# Keyboard.net
KiCad netlist of a schematic drawn in Altium Designer
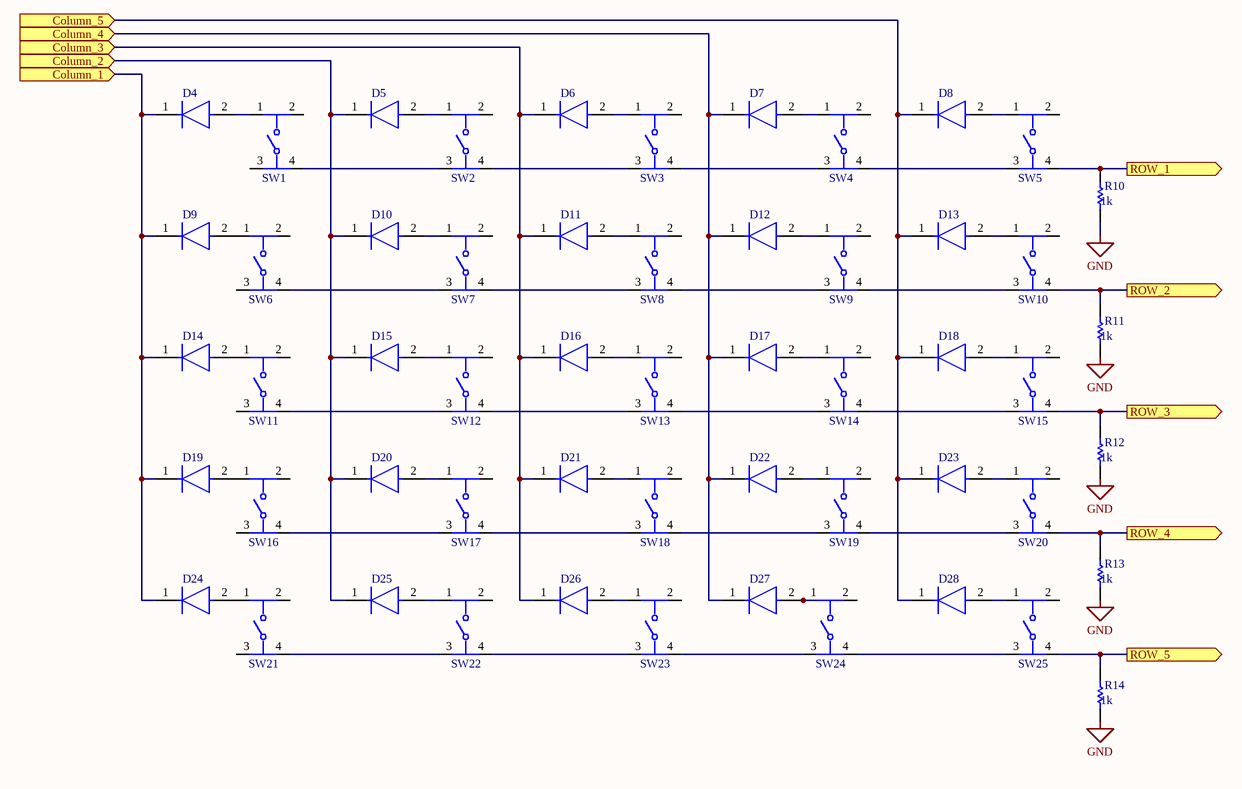
[diagram p0: Keyboard.SchDoc]

(export (version "E")
  (design (tool "Eeschema 10.0.6"))
  (components
    (comp (ref "D4")
      (value "TS4148 RYG")
      (footprint "FP-TS4148_RYG-MFG")
      (description "Rectifier Diode Switching 75V 0.15A 4ns 2-Pin Case 0805(2012Metric) T/R")
      (libsource (lib "Altium Content Vault") (part "d7152d700b627762746794eb795d46e"))
    )
    (comp (ref "D5")
      (value "TS4148 RYG")
      (footprint "FP-TS4148_RYG-MFG")
      (description "Rectifier Diode Switching 75V 0.15A 4ns 2-Pin Case 0805(2012Metric) T/R")
      (libsource (lib "Altium Content Vault") (part "d7152d700b627762746794eb795d46e"))
    )
    (comp (ref "D6")
      (value "TS4148 RYG")
      (footprint "FP-TS4148_RYG-MFG")
      (description "Rectifier Diode Switching 75V 0.15A 4ns 2-Pin Case 0805(2012Metric) T/R")
      (libsource (lib "Altium Content Vault") (part "d7152d700b627762746794eb795d46e"))
    )
    (comp (ref "D7")
      (value "TS4148 RYG")
      (footprint "FP-TS4148_RYG-MFG")
      (description "Rectifier Diode Switching 75V 0.15A 4ns 2-Pin Case 0805(2012Metric) T/R")
      (libsource (lib "Altium Content Vault") (part "d7152d700b627762746794eb795d46e"))
    )
    (comp (ref "D8")
      (value "TS4148 RYG")
      (footprint "FP-TS4148_RYG-MFG")
      (description "Rectifier Diode Switching 75V 0.15A 4ns 2-Pin Case 0805(2012Metric) T/R")
      (libsource (lib "Altium Content Vault") (part "d7152d700b627762746794eb795d46e"))
    )
    (comp (ref "D9")
      (value "TS4148 RYG")
      (footprint "FP-TS4148_RYG-MFG")
      (description "Rectifier Diode Switching 75V 0.15A 4ns 2-Pin Case 0805(2012Metric) T/R")
      (libsource (lib "Altium Content Vault") (part "d7152d700b627762746794eb795d46e"))
    )
    (comp (ref "D10")
      (value "TS4148 RYG")
      (footprint "FP-TS4148_RYG-MFG")
      (description "Rectifier Diode Switching 75V 0.15A 4ns 2-Pin Case 0805(2012Metric) T/R")
      (libsource (lib "Altium Content Vault") (part "d7152d700b627762746794eb795d46e"))
    )
    (comp (ref "D11")
      (value "TS4148 RYG")
      (footprint "FP-TS4148_RYG-MFG")
      (description "Rectifier Diode Switching 75V 0.15A 4ns 2-Pin Case 0805(2012Metric) T/R")
      (libsource (lib "Altium Content Vault") (part "d7152d700b627762746794eb795d46e"))
    )
    (comp (ref "D12")
      (value "TS4148 RYG")
      (footprint "FP-TS4148_RYG-MFG")
      (description "Rectifier Diode Switching 75V 0.15A 4ns 2-Pin Case 0805(2012Metric) T/R")
      (libsource (lib "Altium Content Vault") (part "d7152d700b627762746794eb795d46e"))
    )
    (comp (ref "D13")
      (value "TS4148 RYG")
      (footprint "FP-TS4148_RYG-MFG")
      (description "Rectifier Diode Switching 75V 0.15A 4ns 2-Pin Case 0805(2012Metric) T/R")
      (libsource (lib "Altium Content Vault") (part "d7152d700b627762746794eb795d46e"))
    )
    (comp (ref "D14")
      (value "TS4148 RYG")
      (footprint "FP-TS4148_RYG-MFG")
      (description "Rectifier Diode Switching 75V 0.15A 4ns 2-Pin Case 0805(2012Metric) T/R")
      (libsource (lib "Altium Content Vault") (part "d7152d700b627762746794eb795d46e"))
    )
    (comp (ref "D15")
      (value "TS4148 RYG")
      (footprint "FP-TS4148_RYG-MFG")
      (description "Rectifier Diode Switching 75V 0.15A 4ns 2-Pin Case 0805(2012Metric) T/R")
      (libsource (lib "Altium Content Vault") (part "d7152d700b627762746794eb795d46e"))
    )
    (comp (ref "D16")
      (value "TS4148 RYG")
      (footprint "FP-TS4148_RYG-MFG")
      (description "Rectifier Diode Switching 75V 0.15A 4ns 2-Pin Case 0805(2012Metric) T/R")
      (libsource (lib "Altium Content Vault") (part "d7152d700b627762746794eb795d46e"))
    )
    (comp (ref "D17")
      (value "TS4148 RYG")
      (footprint "FP-TS4148_RYG-MFG")
      (description "Rectifier Diode Switching 75V 0.15A 4ns 2-Pin Case 0805(2012Metric) T/R")
      (libsource (lib "Altium Content Vault") (part "d7152d700b627762746794eb795d46e"))
    )
    (comp (ref "D18")
      (value "TS4148 RYG")
      (footprint "FP-TS4148_RYG-MFG")
      (description "Rectifier Diode Switching 75V 0.15A 4ns 2-Pin Case 0805(2012Metric) T/R")
      (libsource (lib "Altium Content Vault") (part "d7152d700b627762746794eb795d46e"))
    )
    (comp (ref "D19")
      (value "TS4148 RYG")
      (footprint "FP-TS4148_RYG-MFG")
      (description "Rectifier Diode Switching 75V 0.15A 4ns 2-Pin Case 0805(2012Metric) T/R")
      (libsource (lib "Altium Content Vault") (part "d7152d700b627762746794eb795d46e"))
    )
    (comp (ref "D20")
      (value "TS4148 RYG")
      (footprint "FP-TS4148_RYG-MFG")
      (description "Rectifier Diode Switching 75V 0.15A 4ns 2-Pin Case 0805(2012Metric) T/R")
      (libsource (lib "Altium Content Vault") (part "d7152d700b627762746794eb795d46e"))
    )
    (comp (ref "D21")
      (value "TS4148 RYG")
      (footprint "FP-TS4148_RYG-MFG")
      (description "Rectifier Diode Switching 75V 0.15A 4ns 2-Pin Case 0805(2012Metric) T/R")
      (libsource (lib "Altium Content Vault") (part "d7152d700b627762746794eb795d46e"))
    )
    (comp (ref "D22")
      (value "TS4148 RYG")
      (footprint "FP-TS4148_RYG-MFG")
      (description "Rectifier Diode Switching 75V 0.15A 4ns 2-Pin Case 0805(2012Metric) T/R")
      (libsource (lib "Altium Content Vault") (part "d7152d700b627762746794eb795d46e"))
    )
    (comp (ref "D23")
      (value "TS4148 RYG")
      (footprint "FP-TS4148_RYG-MFG")
      (description "Rectifier Diode Switching 75V 0.15A 4ns 2-Pin Case 0805(2012Metric) T/R")
      (libsource (lib "Altium Content Vault") (part "d7152d700b627762746794eb795d46e"))
    )
    (comp (ref "D24")
      (value "TS4148 RYG")
      (footprint "FP-TS4148_RYG-MFG")
      (description "Rectifier Diode Switching 75V 0.15A 4ns 2-Pin Case 0805(2012Metric) T/R")
      (libsource (lib "Altium Content Vault") (part "d7152d700b627762746794eb795d46e"))
    )
    (comp (ref "D25")
      (value "TS4148 RYG")
      (footprint "FP-TS4148_RYG-MFG")
      (description "Rectifier Diode Switching 75V 0.15A 4ns 2-Pin Case 0805(2012Metric) T/R")
      (libsource (lib "Altium Content Vault") (part "d7152d700b627762746794eb795d46e"))
    )
    (comp (ref "D26")
      (value "TS4148 RYG")
      (footprint "FP-TS4148_RYG-MFG")
      (description "Rectifier Diode Switching 75V 0.15A 4ns 2-Pin Case 0805(2012Metric) T/R")
      (libsource (lib "Altium Content Vault") (part "d7152d700b627762746794eb795d46e"))
    )
    (comp (ref "D27")
      (value "TS4148 RYG")
      (footprint "FP-TS4148_RYG-MFG")
      (description "Rectifier Diode Switching 75V 0.15A 4ns 2-Pin Case 0805(2012Metric) T/R")
      (libsource (lib "Altium Content Vault") (part "d7152d700b627762746794eb795d46e"))
    )
    (comp (ref "D28")
      (value "TS4148 RYG")
      (footprint "FP-TS4148_RYG-MFG")
      (description "Rectifier Diode Switching 75V 0.15A 4ns 2-Pin Case 0805(2012Metric) T/R")
      (libsource (lib "Altium Content Vault") (part "d7152d700b627762746794eb795d46e"))
    )
    (comp (ref "R10")
      (value "RC0805FR-071KL")
      (footprint "RESC2013X60X35ML10T20")
      (description "Chip Resistor, 1 KOhm, +/- 1%, 125 mW, -55 to 155 degC, 0805 (2012 Metric), RoHS, Tape and Reel")
      (fields
        (field (name "RESISTANCE") "1k")
        (field (name "TOLERANCE") "1%")
        (field (name "MANUFACTURER") "Yageo")
      )
      (libsource (lib "Altium Content Vault") (part "RES-2"))
    )
    (comp (ref "R11")
      (value "RC0805FR-071KL")
      (footprint "RESC2013X60X35ML10T20")
      (description "Chip Resistor, 1 KOhm, +/- 1%, 125 mW, -55 to 155 degC, 0805 (2012 Metric), RoHS, Tape and Reel")
      (fields
        (field (name "RESISTANCE") "1k")
        (field (name "TOLERANCE") "1%")
        (field (name "MANUFACTURER") "Yageo")
      )
      (libsource (lib "Altium Content Vault") (part "RES-2"))
    )
    (comp (ref "R12")
      (value "RC0805FR-071KL")
      (footprint "RESC2013X60X35ML10T20")
      (description "Chip Resistor, 1 KOhm, +/- 1%, 125 mW, -55 to 155 degC, 0805 (2012 Metric), RoHS, Tape and Reel")
      (fields
        (field (name "RESISTANCE") "1k")
        (field (name "TOLERANCE") "1%")
        (field (name "MANUFACTURER") "Yageo")
      )
      (libsource (lib "Altium Content Vault") (part "RES-2"))
    )
    (comp (ref "R13")
      (value "RC0805FR-071KL")
      (footprint "RESC2013X60X35ML10T20")
      (description "Chip Resistor, 1 KOhm, +/- 1%, 125 mW, -55 to 155 degC, 0805 (2012 Metric), RoHS, Tape and Reel")
      (fields
        (field (name "RESISTANCE") "1k")
        (field (name "TOLERANCE") "1%")
        (field (name "MANUFACTURER") "Yageo")
      )
      (libsource (lib "Altium Content Vault") (part "RES-2"))
    )
    (comp (ref "R14")
      (value "RC0805FR-071KL")
      (footprint "RESC2013X60X35ML10T20")
      (description "Chip Resistor, 1 KOhm, +/- 1%, 125 mW, -55 to 155 degC, 0805 (2012 Metric), RoHS, Tape and Reel")
      (fields
        (field (name "RESISTANCE") "1k")
        (field (name "TOLERANCE") "1%")
        (field (name "MANUFACTURER") "Yageo")
      )
      (libsource (lib "Altium Content Vault") (part "RES-2"))
    )
    (comp (ref "SW1")
      (value "PTS645SM43SMTR92LFS")
      (footprint "FP-PTS645SM43SMTR92LFS-MFG")
      (description "SWITCH TACTILE SPST-NO 0.05A 12V")
      (libsource (lib "Altium Content Vault") (part "1adf0dd01260c80cf25a44bfd6b99ba"))
    )
    (comp (ref "SW2")
      (value "PTS645SM43SMTR92LFS")
      (footprint "FP-PTS645SM43SMTR92LFS-MFG")
      (description "SWITCH TACTILE SPST-NO 0.05A 12V")
      (libsource (lib "Altium Content Vault") (part "1adf0dd01260c80cf25a44bfd6b99ba"))
    )
    (comp (ref "SW3")
      (value "PTS645SM43SMTR92LFS")
      (footprint "FP-PTS645SM43SMTR92LFS-MFG")
      (description "SWITCH TACTILE SPST-NO 0.05A 12V")
      (libsource (lib "Altium Content Vault") (part "1adf0dd01260c80cf25a44bfd6b99ba"))
    )
    (comp (ref "SW4")
      (value "PTS645SM43SMTR92LFS")
      (footprint "FP-PTS645SM43SMTR92LFS-MFG")
      (description "SWITCH TACTILE SPST-NO 0.05A 12V")
      (libsource (lib "Altium Content Vault") (part "1adf0dd01260c80cf25a44bfd6b99ba"))
    )
    (comp (ref "SW5")
      (value "PTS645SM43SMTR92LFS")
      (footprint "FP-PTS645SM43SMTR92LFS-MFG")
      (description "SWITCH TACTILE SPST-NO 0.05A 12V")
      (libsource (lib "Altium Content Vault") (part "1adf0dd01260c80cf25a44bfd6b99ba"))
    )
    (comp (ref "SW6")
      (value "PTS645SM43SMTR92LFS")
      (footprint "FP-PTS645SM43SMTR92LFS-MFG")
      (description "SWITCH TACTILE SPST-NO 0.05A 12V")
      (libsource (lib "Altium Content Vault") (part "1adf0dd01260c80cf25a44bfd6b99ba"))
    )
    (comp (ref "SW7")
      (value "PTS645SM43SMTR92LFS")
      (footprint "FP-PTS645SM43SMTR92LFS-MFG")
      (description "SWITCH TACTILE SPST-NO 0.05A 12V")
      (libsource (lib "Altium Content Vault") (part "1adf0dd01260c80cf25a44bfd6b99ba"))
    )
    (comp (ref "SW8")
      (value "PTS645SM43SMTR92LFS")
      (footprint "FP-PTS645SM43SMTR92LFS-MFG")
      (description "SWITCH TACTILE SPST-NO 0.05A 12V")
      (libsource (lib "Altium Content Vault") (part "1adf0dd01260c80cf25a44bfd6b99ba"))
    )
    (comp (ref "SW9")
      (value "PTS645SM43SMTR92LFS")
      (footprint "FP-PTS645SM43SMTR92LFS-MFG")
      (description "SWITCH TACTILE SPST-NO 0.05A 12V")
      (libsource (lib "Altium Content Vault") (part "1adf0dd01260c80cf25a44bfd6b99ba"))
    )
    (comp (ref "SW10")
      (value "PTS645SM43SMTR92LFS")
      (footprint "FP-PTS645SM43SMTR92LFS-MFG")
      (description "SWITCH TACTILE SPST-NO 0.05A 12V")
      (libsource (lib "Altium Content Vault") (part "1adf0dd01260c80cf25a44bfd6b99ba"))
    )
    (comp (ref "SW11")
      (value "PTS645SM43SMTR92LFS")
      (footprint "FP-PTS645SM43SMTR92LFS-MFG")
      (description "SWITCH TACTILE SPST-NO 0.05A 12V")
      (libsource (lib "Altium Content Vault") (part "1adf0dd01260c80cf25a44bfd6b99ba"))
    )
    (comp (ref "SW12")
      (value "PTS645SM43SMTR92LFS")
      (footprint "FP-PTS645SM43SMTR92LFS-MFG")
      (description "SWITCH TACTILE SPST-NO 0.05A 12V")
      (libsource (lib "Altium Content Vault") (part "1adf0dd01260c80cf25a44bfd6b99ba"))
    )
    (comp (ref "SW13")
      (value "PTS645SM43SMTR92LFS")
      (footprint "FP-PTS645SM43SMTR92LFS-MFG")
      (description "SWITCH TACTILE SPST-NO 0.05A 12V")
      (libsource (lib "Altium Content Vault") (part "1adf0dd01260c80cf25a44bfd6b99ba"))
    )
    (comp (ref "SW14")
      (value "PTS645SM43SMTR92LFS")
      (footprint "FP-PTS645SM43SMTR92LFS-MFG")
      (description "SWITCH TACTILE SPST-NO 0.05A 12V")
      (libsource (lib "Altium Content Vault") (part "1adf0dd01260c80cf25a44bfd6b99ba"))
    )
    (comp (ref "SW15")
      (value "PTS645SM43SMTR92LFS")
      (footprint "FP-PTS645SM43SMTR92LFS-MFG")
      (description "SWITCH TACTILE SPST-NO 0.05A 12V")
      (libsource (lib "Altium Content Vault") (part "1adf0dd01260c80cf25a44bfd6b99ba"))
    )
    (comp (ref "SW16")
      (value "PTS645SM43SMTR92LFS")
      (footprint "FP-PTS645SM43SMTR92LFS-MFG")
      (description "SWITCH TACTILE SPST-NO 0.05A 12V")
      (libsource (lib "Altium Content Vault") (part "1adf0dd01260c80cf25a44bfd6b99ba"))
    )
    (comp (ref "SW17")
      (value "PTS645SM43SMTR92LFS")
      (footprint "FP-PTS645SM43SMTR92LFS-MFG")
      (description "SWITCH TACTILE SPST-NO 0.05A 12V")
      (libsource (lib "Altium Content Vault") (part "1adf0dd01260c80cf25a44bfd6b99ba"))
    )
    (comp (ref "SW18")
      (value "PTS645SM43SMTR92LFS")
      (footprint "FP-PTS645SM43SMTR92LFS-MFG")
      (description "SWITCH TACTILE SPST-NO 0.05A 12V")
      (libsource (lib "Altium Content Vault") (part "1adf0dd01260c80cf25a44bfd6b99ba"))
    )
    (comp (ref "SW19")
      (value "PTS645SM43SMTR92LFS")
      (footprint "FP-PTS645SM43SMTR92LFS-MFG")
      (description "SWITCH TACTILE SPST-NO 0.05A 12V")
      (libsource (lib "Altium Content Vault") (part "1adf0dd01260c80cf25a44bfd6b99ba"))
    )
    (comp (ref "SW20")
      (value "PTS645SM43SMTR92LFS")
      (footprint "FP-PTS645SM43SMTR92LFS-MFG")
      (description "SWITCH TACTILE SPST-NO 0.05A 12V")
      (libsource (lib "Altium Content Vault") (part "1adf0dd01260c80cf25a44bfd6b99ba"))
    )
    (comp (ref "SW21")
      (value "PTS645SM43SMTR92LFS")
      (footprint "FP-PTS645SM43SMTR92LFS-MFG")
      (description "SWITCH TACTILE SPST-NO 0.05A 12V")
      (libsource (lib "Altium Content Vault") (part "1adf0dd01260c80cf25a44bfd6b99ba"))
    )
    (comp (ref "SW22")
      (value "PTS645SM43SMTR92LFS")
      (footprint "FP-PTS645SM43SMTR92LFS-MFG")
      (description "SWITCH TACTILE SPST-NO 0.05A 12V")
      (libsource (lib "Altium Content Vault") (part "1adf0dd01260c80cf25a44bfd6b99ba"))
    )
    (comp (ref "SW23")
      (value "PTS645SM43SMTR92LFS")
      (footprint "FP-PTS645SM43SMTR92LFS-MFG")
      (description "SWITCH TACTILE SPST-NO 0.05A 12V")
      (libsource (lib "Altium Content Vault") (part "1adf0dd01260c80cf25a44bfd6b99ba"))
    )
    (comp (ref "SW24")
      (value "PTS645SM43SMTR92LFS")
      (footprint "FP-PTS645SM43SMTR92LFS-MFG")
      (description "SWITCH TACTILE SPST-NO 0.05A 12V")
      (libsource (lib "Altium Content Vault") (part "1adf0dd01260c80cf25a44bfd6b99ba"))
    )
    (comp (ref "SW25")
      (value "PTS645SM43SMTR92LFS")
      (footprint "FP-PTS645SM43SMTR92LFS-MFG")
      (description "SWITCH TACTILE SPST-NO 0.05A 12V")
      (libsource (lib "Altium Content Vault") (part "1adf0dd01260c80cf25a44bfd6b99ba"))
    )
  )
  (nets
    (net (code "1") (name "/Column_1") (class "Default")
      (node (ref "D14") (pin "1") (pinfunction "C_1") (pintype "passive"))
      (node (ref "D19") (pin "1") (pinfunction "C_1") (pintype "passive"))
      (node (ref "D24") (pin "1") (pinfunction "C_1") (pintype "passive"))
      (node (ref "D4") (pin "1") (pinfunction "C_1") (pintype "passive"))
      (node (ref "D9") (pin "1") (pinfunction "C_1") (pintype "passive"))
    )
    (net (code "2") (name "/Column_2") (class "Default")
      (node (ref "D10") (pin "1") (pinfunction "C_1") (pintype "passive"))
      (node (ref "D15") (pin "1") (pinfunction "C_1") (pintype "passive"))
      (node (ref "D20") (pin "1") (pinfunction "C_1") (pintype "passive"))
      (node (ref "D25") (pin "1") (pinfunction "C_1") (pintype "passive"))
      (node (ref "D5") (pin "1") (pinfunction "C_1") (pintype "passive"))
    )
    (net (code "3") (name "/Column_3") (class "Default")
      (node (ref "D11") (pin "1") (pinfunction "C_1") (pintype "passive"))
      (node (ref "D16") (pin "1") (pinfunction "C_1") (pintype "passive"))
      (node (ref "D21") (pin "1") (pinfunction "C_1") (pintype "passive"))
      (node (ref "D26") (pin "1") (pinfunction "C_1") (pintype "passive"))
      (node (ref "D6") (pin "1") (pinfunction "C_1") (pintype "passive"))
    )
    (net (code "4") (name "/Column_4") (class "Default")
      (node (ref "D12") (pin "1") (pinfunction "C_1") (pintype "passive"))
      (node (ref "D17") (pin "1") (pinfunction "C_1") (pintype "passive"))
      (node (ref "D22") (pin "1") (pinfunction "C_1") (pintype "passive"))
      (node (ref "D27") (pin "1") (pinfunction "C_1") (pintype "passive"))
      (node (ref "D7") (pin "1") (pinfunction "C_1") (pintype "passive"))
    )
    (net (code "5") (name "/Column_5") (class "Default")
      (node (ref "D13") (pin "1") (pinfunction "C_1") (pintype "passive"))
      (node (ref "D18") (pin "1") (pinfunction "C_1") (pintype "passive"))
      (node (ref "D23") (pin "1") (pinfunction "C_1") (pintype "passive"))
      (node (ref "D28") (pin "1") (pinfunction "C_1") (pintype "passive"))
      (node (ref "D8") (pin "1") (pinfunction "C_1") (pintype "passive"))
    )
    (net (code "6") (name "/ROW_1") (class "Default")
      (node (ref "R10") (pin "2") (pinfunction "2_2") (pintype "passive"))
      (node (ref "SW5") (pin "4") (pinfunction "4_4") (pintype "passive"))
    )
    (net (code "7") (name "/ROW_2") (class "Default")
      (node (ref "R11") (pin "2") (pinfunction "2_2") (pintype "passive"))
      (node (ref "SW10") (pin "4") (pinfunction "4_4") (pintype "passive"))
    )
    (net (code "8") (name "/ROW_3") (class "Default")
      (node (ref "R12") (pin "2") (pinfunction "2_2") (pintype "passive"))
      (node (ref "SW15") (pin "4") (pinfunction "4_4") (pintype "passive"))
    )
    (net (code "9") (name "/ROW_4") (class "Default")
      (node (ref "R13") (pin "2") (pinfunction "2_2") (pintype "passive"))
      (node (ref "SW20") (pin "4") (pinfunction "4_4") (pintype "passive"))
    )
    (net (code "10") (name "/ROW_5") (class "Default")
      (node (ref "R14") (pin "2") (pinfunction "2_2") (pintype "passive"))
      (node (ref "SW25") (pin "4") (pinfunction "4_4") (pintype "passive"))
    )
    (net (code "11") (name "GND") (class "Default")
      (node (ref "R10") (pin "1") (pinfunction "1_1") (pintype "passive"))
      (node (ref "R11") (pin "1") (pinfunction "1_1") (pintype "passive"))
      (node (ref "R12") (pin "1") (pinfunction "1_1") (pintype "passive"))
      (node (ref "R13") (pin "1") (pinfunction "1_1") (pintype "passive"))
      (node (ref "R14") (pin "1") (pinfunction "1_1") (pintype "passive"))
    )
    (net (code "12") (name "Net-(D4-A)") (class "Default")
      (node (ref "D4") (pin "2") (pinfunction "A_2") (pintype "passive"))
      (node (ref "SW1") (pin "1") (pinfunction "1_1") (pintype "passive"))
    )
    (net (code "13") (name "Net-(D5-A)") (class "Default")
      (node (ref "D5") (pin "2") (pinfunction "A_2") (pintype "passive"))
      (node (ref "SW2") (pin "1") (pinfunction "1_1") (pintype "passive"))
    )
    (net (code "14") (name "Net-(D6-A)") (class "Default")
      (node (ref "D6") (pin "2") (pinfunction "A_2") (pintype "passive"))
      (node (ref "SW3") (pin "1") (pinfunction "1_1") (pintype "passive"))
    )
    (net (code "15") (name "Net-(D7-A)") (class "Default")
      (node (ref "D7") (pin "2") (pinfunction "A_2") (pintype "passive"))
      (node (ref "SW4") (pin "1") (pinfunction "1_1") (pintype "passive"))
    )
    (net (code "16") (name "Net-(D8-A)") (class "Default")
      (node (ref "D8") (pin "2") (pinfunction "A_2") (pintype "passive"))
      (node (ref "SW5") (pin "1") (pinfunction "1_1") (pintype "passive"))
    )
    (net (code "17") (name "Net-(D9-A)") (class "Default")
      (node (ref "D9") (pin "2") (pinfunction "A_2") (pintype "passive"))
      (node (ref "SW6") (pin "1") (pinfunction "1_1") (pintype "passive"))
    )
    (net (code "18") (name "Net-(D10-A)") (class "Default")
      (node (ref "D10") (pin "2") (pinfunction "A_2") (pintype "passive"))
      (node (ref "SW7") (pin "1") (pinfunction "1_1") (pintype "passive"))
    )
    (net (code "19") (name "Net-(D11-A)") (class "Default")
      (node (ref "D11") (pin "2") (pinfunction "A_2") (pintype "passive"))
      (node (ref "SW8") (pin "1") (pinfunction "1_1") (pintype "passive"))
    )
    (net (code "20") (name "Net-(D12-A)") (class "Default")
      (node (ref "D12") (pin "2") (pinfunction "A_2") (pintype "passive"))
      (node (ref "SW9") (pin "1") (pinfunction "1_1") (pintype "passive"))
    )
    (net (code "21") (name "Net-(D13-A)") (class "Default")
      (node (ref "D13") (pin "2") (pinfunction "A_2") (pintype "passive"))
      (node (ref "SW10") (pin "1") (pinfunction "1_1") (pintype "passive"))
    )
    (net (code "22") (name "Net-(D14-A)") (class "Default")
      (node (ref "D14") (pin "2") (pinfunction "A_2") (pintype "passive"))
      (node (ref "SW11") (pin "1") (pinfunction "1_1") (pintype "passive"))
    )
    (net (code "23") (name "Net-(D15-A)") (class "Default")
      (node (ref "D15") (pin "2") (pinfunction "A_2") (pintype "passive"))
      (node (ref "SW12") (pin "1") (pinfunction "1_1") (pintype "passive"))
    )
    (net (code "24") (name "Net-(D16-A)") (class "Default")
      (node (ref "D16") (pin "2") (pinfunction "A_2") (pintype "passive"))
      (node (ref "SW13") (pin "1") (pinfunction "1_1") (pintype "passive"))
    )
    (net (code "25") (name "Net-(D17-A)") (class "Default")
      (node (ref "D17") (pin "2") (pinfunction "A_2") (pintype "passive"))
      (node (ref "SW14") (pin "1") (pinfunction "1_1") (pintype "passive"))
    )
    (net (code "26") (name "Net-(D18-A)") (class "Default")
      (node (ref "D18") (pin "2") (pinfunction "A_2") (pintype "passive"))
      (node (ref "SW15") (pin "1") (pinfunction "1_1") (pintype "passive"))
    )
    (net (code "27") (name "Net-(D19-A)") (class "Default")
      (node (ref "D19") (pin "2") (pinfunction "A_2") (pintype "passive"))
      (node (ref "SW16") (pin "1") (pinfunction "1_1") (pintype "passive"))
    )
    (net (code "28") (name "Net-(D20-A)") (class "Default")
      (node (ref "D20") (pin "2") (pinfunction "A_2") (pintype "passive"))
      (node (ref "SW17") (pin "1") (pinfunction "1_1") (pintype "passive"))
    )
    (net (code "29") (name "Net-(D21-A)") (class "Default")
      (node (ref "D21") (pin "2") (pinfunction "A_2") (pintype "passive"))
      (node (ref "SW18") (pin "1") (pinfunction "1_1") (pintype "passive"))
    )
    (net (code "30") (name "Net-(D22-A)") (class "Default")
      (node (ref "D22") (pin "2") (pinfunction "A_2") (pintype "passive"))
      (node (ref "SW19") (pin "1") (pinfunction "1_1") (pintype "passive"))
    )
    (net (code "31") (name "Net-(D23-A)") (class "Default")
      (node (ref "D23") (pin "2") (pinfunction "A_2") (pintype "passive"))
      (node (ref "SW20") (pin "1") (pinfunction "1_1") (pintype "passive"))
    )
    (net (code "32") (name "Net-(D24-A)") (class "Default")
      (node (ref "D24") (pin "2") (pinfunction "A_2") (pintype "passive"))
      (node (ref "SW21") (pin "1") (pinfunction "1_1") (pintype "passive"))
    )
    (net (code "33") (name "Net-(D25-A)") (class "Default")
      (node (ref "D25") (pin "2") (pinfunction "A_2") (pintype "passive"))
      (node (ref "SW22") (pin "1") (pinfunction "1_1") (pintype "passive"))
    )
    (net (code "34") (name "Net-(D26-A)") (class "Default")
      (node (ref "D26") (pin "2") (pinfunction "A_2") (pintype "passive"))
      (node (ref "SW23") (pin "1") (pinfunction "1_1") (pintype "passive"))
    )
    (net (code "35") (name "Net-(D27-A)") (class "Default")
      (node (ref "D27") (pin "2") (pinfunction "A_2") (pintype "passive"))
      (node (ref "SW24") (pin "1") (pinfunction "1_1") (pintype "passive"))
    )
    (net (code "36") (name "Net-(D28-A)") (class "Default")
      (node (ref "D28") (pin "2") (pinfunction "A_2") (pintype "passive"))
      (node (ref "SW25") (pin "1") (pinfunction "1_1") (pintype "passive"))
    )
    (net (code "37") (name "Net-(SW1-Pad4)") (class "Default")
      (node (ref "SW1") (pin "4") (pinfunction "4_4") (pintype "passive"))
      (node (ref "SW2") (pin "3") (pinfunction "3_3") (pintype "passive"))
    )
    (net (code "38") (name "Net-(SW2-Pad4)") (class "Default")
      (node (ref "SW2") (pin "4") (pinfunction "4_4") (pintype "passive"))
      (node (ref "SW3") (pin "3") (pinfunction "3_3") (pintype "passive"))
    )
    (net (code "39") (name "Net-(SW3-Pad4)") (class "Default")
      (node (ref "SW3") (pin "4") (pinfunction "4_4") (pintype "passive"))
      (node (ref "SW4") (pin "3") (pinfunction "3_3") (pintype "passive"))
    )
    (net (code "40") (name "Net-(SW4-Pad4)") (class "Default")
      (node (ref "SW4") (pin "4") (pinfunction "4_4") (pintype "passive"))
      (node (ref "SW5") (pin "3") (pinfunction "3_3") (pintype "passive"))
    )
    (net (code "41") (name "Net-(SW6-Pad4)") (class "Default")
      (node (ref "SW6") (pin "4") (pinfunction "4_4") (pintype "passive"))
      (node (ref "SW7") (pin "3") (pinfunction "3_3") (pintype "passive"))
    )
    (net (code "42") (name "Net-(SW7-Pad4)") (class "Default")
      (node (ref "SW7") (pin "4") (pinfunction "4_4") (pintype "passive"))
      (node (ref "SW8") (pin "3") (pinfunction "3_3") (pintype "passive"))
    )
    (net (code "43") (name "Net-(SW8-Pad4)") (class "Default")
      (node (ref "SW8") (pin "4") (pinfunction "4_4") (pintype "passive"))
      (node (ref "SW9") (pin "3") (pinfunction "3_3") (pintype "passive"))
    )
    (net (code "44") (name "Net-(SW10-Pad3)") (class "Default")
      (node (ref "SW10") (pin "3") (pinfunction "3_3") (pintype "passive"))
      (node (ref "SW9") (pin "4") (pinfunction "4_4") (pintype "passive"))
    )
    (net (code "45") (name "Net-(SW11-Pad4)") (class "Default")
      (node (ref "SW11") (pin "4") (pinfunction "4_4") (pintype "passive"))
      (node (ref "SW12") (pin "3") (pinfunction "3_3") (pintype "passive"))
    )
    (net (code "46") (name "Net-(SW12-Pad4)") (class "Default")
      (node (ref "SW12") (pin "4") (pinfunction "4_4") (pintype "passive"))
      (node (ref "SW13") (pin "3") (pinfunction "3_3") (pintype "passive"))
    )
    (net (code "47") (name "Net-(SW13-Pad4)") (class "Default")
      (node (ref "SW13") (pin "4") (pinfunction "4_4") (pintype "passive"))
      (node (ref "SW14") (pin "3") (pinfunction "3_3") (pintype "passive"))
    )
    (net (code "48") (name "Net-(SW14-Pad4)") (class "Default")
      (node (ref "SW14") (pin "4") (pinfunction "4_4") (pintype "passive"))
      (node (ref "SW15") (pin "3") (pinfunction "3_3") (pintype "passive"))
    )
    (net (code "49") (name "Net-(SW16-Pad4)") (class "Default")
      (node (ref "SW16") (pin "4") (pinfunction "4_4") (pintype "passive"))
      (node (ref "SW17") (pin "3") (pinfunction "3_3") (pintype "passive"))
    )
    (net (code "50") (name "Net-(SW17-Pad4)") (class "Default")
      (node (ref "SW17") (pin "4") (pinfunction "4_4") (pintype "passive"))
      (node (ref "SW18") (pin "3") (pinfunction "3_3") (pintype "passive"))
    )
    (net (code "51") (name "Net-(SW18-Pad4)") (class "Default")
      (node (ref "SW18") (pin "4") (pinfunction "4_4") (pintype "passive"))
      (node (ref "SW19") (pin "3") (pinfunction "3_3") (pintype "passive"))
    )
    (net (code "52") (name "Net-(SW19-Pad4)") (class "Default")
      (node (ref "SW19") (pin "4") (pinfunction "4_4") (pintype "passive"))
      (node (ref "SW20") (pin "3") (pinfunction "3_3") (pintype "passive"))
    )
    (net (code "53") (name "Net-(SW21-Pad4)") (class "Default")
      (node (ref "SW21") (pin "4") (pinfunction "4_4") (pintype "passive"))
      (node (ref "SW22") (pin "3") (pinfunction "3_3") (pintype "passive"))
    )
    (net (code "54") (name "Net-(SW22-Pad4)") (class "Default")
      (node (ref "SW22") (pin "4") (pinfunction "4_4") (pintype "passive"))
      (node (ref "SW23") (pin "3") (pinfunction "3_3") (pintype "passive"))
    )
    (net (code "55") (name "Net-(SW23-Pad4)") (class "Default")
      (node (ref "SW23") (pin "4") (pinfunction "4_4") (pintype "passive"))
      (node (ref "SW24") (pin "3") (pinfunction "3_3") (pintype "passive"))
    )
    (net (code "56") (name "Net-(SW24-Pad4)") (class "Default")
      (node (ref "SW24") (pin "4") (pinfunction "4_4") (pintype "passive"))
      (node (ref "SW25") (pin "3") (pinfunction "3_3") (pintype "passive"))
    )
    (net (code "57") (name "unconnected-(SW1-Pad2)") (class "Default")
      (node (ref "SW1") (pin "2") (pinfunction "2_2") (pintype "passive"))
    )
    (net (code "58") (name "unconnected-(SW1-Pad3)") (class "Default")
      (node (ref "SW1") (pin "3") (pinfunction "3_3") (pintype "passive"))
    )
    (net (code "59") (name "unconnected-(SW2-Pad2)") (class "Default")
      (node (ref "SW2") (pin "2") (pinfunction "2_2") (pintype "passive"))
    )
    (net (code "60") (name "unconnected-(SW3-Pad2)") (class "Default")
      (node (ref "SW3") (pin "2") (pinfunction "2_2") (pintype "passive"))
    )
    (net (code "61") (name "unconnected-(SW4-Pad2)") (class "Default")
      (node (ref "SW4") (pin "2") (pinfunction "2_2") (pintype "passive"))
    )
    (net (code "62") (name "unconnected-(SW5-Pad2)") (class "Default")
      (node (ref "SW5") (pin "2") (pinfunction "2_2") (pintype "passive"))
    )
    (net (code "63") (name "unconnected-(SW6-Pad2)") (class "Default")
      (node (ref "SW6") (pin "2") (pinfunction "2_2") (pintype "passive"))
    )
    (net (code "64") (name "unconnected-(SW6-Pad3)") (class "Default")
      (node (ref "SW6") (pin "3") (pinfunction "3_3") (pintype "passive"))
    )
    (net (code "65") (name "unconnected-(SW7-Pad2)") (class "Default")
      (node (ref "SW7") (pin "2") (pinfunction "2_2") (pintype "passive"))
    )
    (net (code "66") (name "unconnected-(SW8-Pad2)") (class "Default")
      (node (ref "SW8") (pin "2") (pinfunction "2_2") (pintype "passive"))
    )
    (net (code "67") (name "unconnected-(SW9-Pad2)") (class "Default")
      (node (ref "SW9") (pin "2") (pinfunction "2_2") (pintype "passive"))
    )
    (net (code "68") (name "unconnected-(SW10-Pad2)") (class "Default")
      (node (ref "SW10") (pin "2") (pinfunction "2_2") (pintype "passive"))
    )
    (net (code "69") (name "unconnected-(SW11-Pad2)") (class "Default")
      (node (ref "SW11") (pin "2") (pinfunction "2_2") (pintype "passive"))
    )
    (net (code "70") (name "unconnected-(SW11-Pad3)") (class "Default")
      (node (ref "SW11") (pin "3") (pinfunction "3_3") (pintype "passive"))
    )
    (net (code "71") (name "unconnected-(SW12-Pad2)") (class "Default")
      (node (ref "SW12") (pin "2") (pinfunction "2_2") (pintype "passive"))
    )
    (net (code "72") (name "unconnected-(SW13-Pad2)") (class "Default")
      (node (ref "SW13") (pin "2") (pinfunction "2_2") (pintype "passive"))
    )
    (net (code "73") (name "unconnected-(SW14-Pad2)") (class "Default")
      (node (ref "SW14") (pin "2") (pinfunction "2_2") (pintype "passive"))
    )
    (net (code "74") (name "unconnected-(SW15-Pad2)") (class "Default")
      (node (ref "SW15") (pin "2") (pinfunction "2_2") (pintype "passive"))
    )
    (net (code "75") (name "unconnected-(SW16-Pad2)") (class "Default")
      (node (ref "SW16") (pin "2") (pinfunction "2_2") (pintype "passive"))
    )
    (net (code "76") (name "unconnected-(SW16-Pad3)") (class "Default")
      (node (ref "SW16") (pin "3") (pinfunction "3_3") (pintype "passive"))
    )
    (net (code "77") (name "unconnected-(SW17-Pad2)") (class "Default")
      (node (ref "SW17") (pin "2") (pinfunction "2_2") (pintype "passive"))
    )
    (net (code "78") (name "unconnected-(SW18-Pad2)") (class "Default")
      (node (ref "SW18") (pin "2") (pinfunction "2_2") (pintype "passive"))
    )
    (net (code "79") (name "unconnected-(SW19-Pad2)") (class "Default")
      (node (ref "SW19") (pin "2") (pinfunction "2_2") (pintype "passive"))
    )
    (net (code "80") (name "unconnected-(SW20-Pad2)") (class "Default")
      (node (ref "SW20") (pin "2") (pinfunction "2_2") (pintype "passive"))
    )
    (net (code "81") (name "unconnected-(SW21-Pad2)") (class "Default")
      (node (ref "SW21") (pin "2") (pinfunction "2_2") (pintype "passive"))
    )
    (net (code "82") (name "unconnected-(SW21-Pad3)") (class "Default")
      (node (ref "SW21") (pin "3") (pinfunction "3_3") (pintype "passive"))
    )
    (net (code "83") (name "unconnected-(SW22-Pad2)") (class "Default")
      (node (ref "SW22") (pin "2") (pinfunction "2_2") (pintype "passive"))
    )
    (net (code "84") (name "unconnected-(SW23-Pad2)") (class "Default")
      (node (ref "SW23") (pin "2") (pinfunction "2_2") (pintype "passive"))
    )
    (net (code "85") (name "unconnected-(SW24-Pad2)") (class "Default")
      (node (ref "SW24") (pin "2") (pinfunction "2_2") (pintype "passive"))
    )
    (net (code "86") (name "unconnected-(SW25-Pad2)") (class "Default")
      (node (ref "SW25") (pin "2") (pinfunction "2_2") (pintype "passive"))
    )
  )
)
